# DRIVER_5V.net
KiCad netlist of a schematic drawn in EAGLE
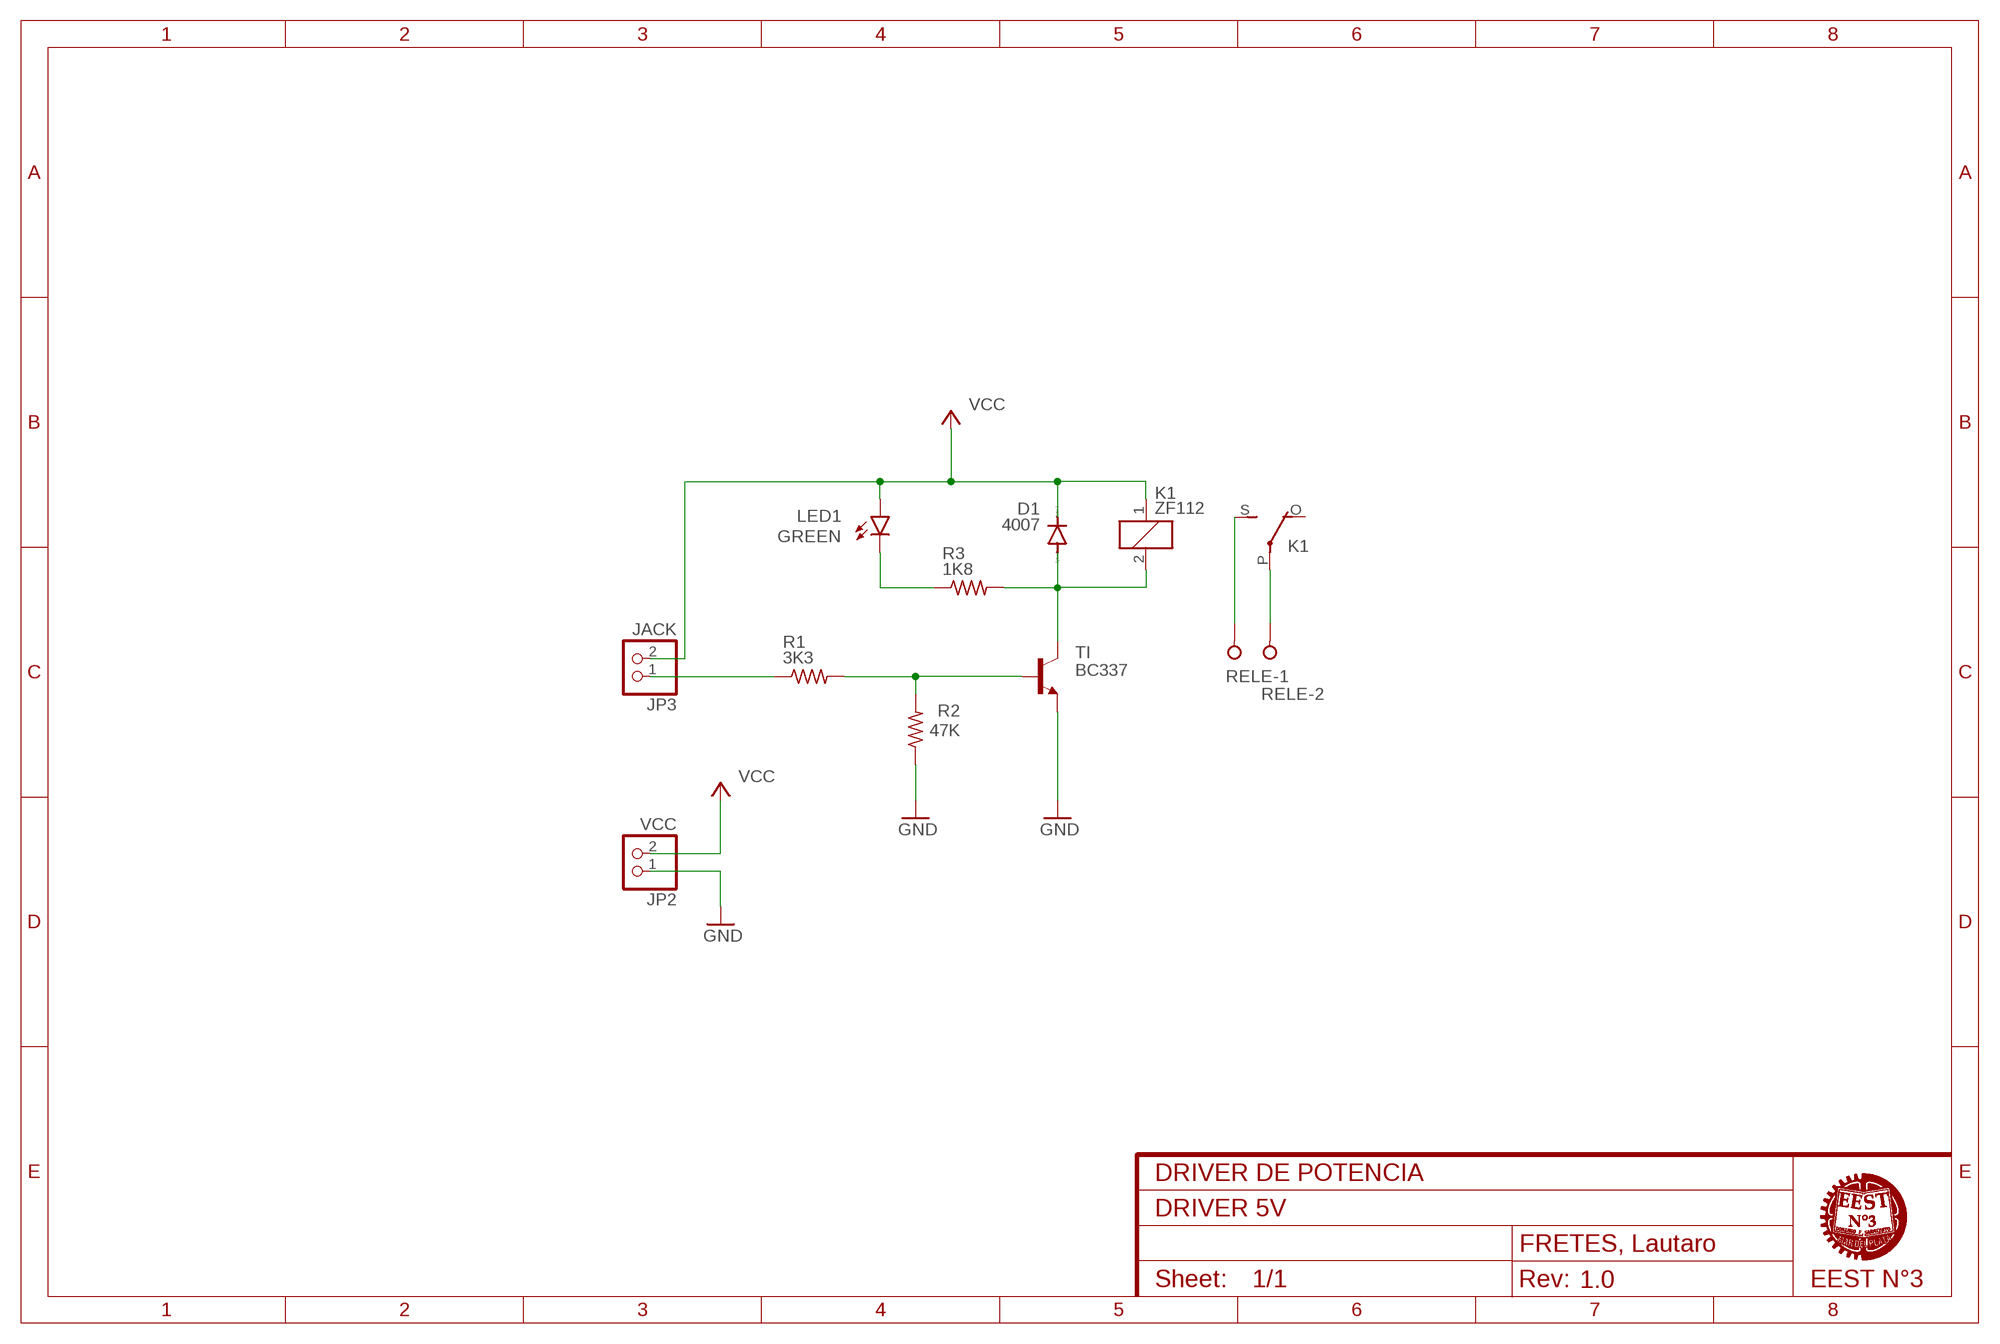
[diagram p0: schematic, sheet 1]

(export (version "E")
  (design (tool "Eeschema 10.0.6"))
  (components
    (comp (ref "D1")
      (value "4007")
      (footprint "eagle-import:DO35-10")
      (libsource (lib "eagle-import") (part "1N4148DO35-10"))
    )
    (comp (ref "JP2")
      (value "VCC")
      (footprint "eagle-import:1X02")
      (libsource (lib "eagle-import") (part "PINHD-1X2"))
    )
    (comp (ref "JP3")
      (value "JACK")
      (footprint "eagle-import:1X02")
      (libsource (lib "eagle-import") (part "PINHD-1X2"))
    )
    (comp (ref "K1")
      (value "ZF112")
      (footprint "eagle-import:ZF112")
      (libsource (lib "eagle-import") (part "ZF112"))
    )
    (comp (ref "LED1")
      (value "GREEN")
      (footprint "eagle-import:LED5MM")
      (libsource (lib "eagle-import") (part "LED5MM"))
    )
    (comp (ref "R1")
      (value "3K3")
      (footprint "eagle-import:0207_10")
      (libsource (lib "eagle-import") (part "R-US_0207/10"))
    )
    (comp (ref "R2")
      (value "47K")
      (footprint "eagle-import:0207_10")
      (libsource (lib "eagle-import") (part "R-US_0207/10"))
    )
    (comp (ref "R3")
      (value "1K8")
      (footprint "eagle-import:0207_10")
      (libsource (lib "eagle-import") (part "R-US_0207/10"))
    )
    (comp (ref "RELE")
      (value "W237-02P")
      (footprint "eagle-import:W237-132")
      (libsource (lib "eagle-import") (part "W237-02P"))
    )
    (comp (ref "TI")
      (value "BC337")
      (footprint "eagle-import:TO92-CBE")
      (libsource (lib "eagle-import") (part "-NPN-TO92-CBE2N4124"))
    )
    (comp (ref "U$1")
      (value "LOGO_EEST_N3")
      (footprint "eagle-import:LOGO_EEST_N3_250")
      (libsource (lib "eagle-import") (part "LOGO_EEST_N3"))
    )
  )
  (nets
    (net (code "1") (name "GND") (class "Default")
      (node (ref "JP2") (pin "1") (pinfunction "1_1") (pintype "passive"))
      (node (ref "R2") (pin "1") (pinfunction "1_1") (pintype "passive"))
      (node (ref "TI") (pin "E") (pinfunction "E_E") (pintype "passive"))
    )
    (net (code "2") (name "Net-(D1-PadA)") (class "Default")
      (node (ref "D1") (pin "A") (pinfunction "A_A") (pintype "passive"))
      (node (ref "K1") (pin "2") (pinfunction "2_2") (pintype "passive"))
      (node (ref "R3") (pin "2") (pinfunction "2_2") (pintype "passive"))
      (node (ref "TI") (pin "C") (pinfunction "C_C") (pintype "passive"))
    )
    (net (code "3") (name "Net-(JP3-Pad1)") (class "Default")
      (node (ref "JP3") (pin "1") (pinfunction "1_1") (pintype "passive"))
      (node (ref "R1") (pin "1") (pinfunction "1_1") (pintype "passive"))
    )
    (net (code "4") (name "Net-(LED1-C)") (class "Default")
      (node (ref "LED1") (pin "K") (pinfunction "C_K") (pintype "passive"))
      (node (ref "R3") (pin "1") (pinfunction "1_1") (pintype "passive"))
    )
    (net (code "5") (name "Net-(R1-Pad2)") (class "Default")
      (node (ref "R1") (pin "2") (pinfunction "2_2") (pintype "passive"))
      (node (ref "R2") (pin "2") (pinfunction "2_2") (pintype "passive"))
      (node (ref "TI") (pin "B") (pinfunction "B_B") (pintype "passive"))
    )
    (net (code "6") (name "Net-(RELEA-KL)") (class "Default")
      (node (ref "K1") (pin "S") (pinfunction "S_S") (pintype "passive"))
      (node (ref "RELE") (pin "1") (pinfunction "KL_1") (pintype "passive"))
    )
    (net (code "7") (name "Net-(RELEB-KL)") (class "Default")
      (node (ref "K1") (pin "P") (pinfunction "P_P") (pintype "passive"))
      (node (ref "RELE") (pin "2") (pinfunction "KL_2") (pintype "passive"))
    )
    (net (code "8") (name "VCC") (class "Default")
      (node (ref "D1") (pin "C") (pinfunction "C_C") (pintype "passive"))
      (node (ref "JP2") (pin "2") (pinfunction "2_2") (pintype "passive"))
      (node (ref "JP3") (pin "2") (pinfunction "2_2") (pintype "passive"))
      (node (ref "K1") (pin "1") (pinfunction "1_1") (pintype "passive"))
      (node (ref "LED1") (pin "A") (pinfunction "A_A") (pintype "passive"))
    )
    (net (code "9") (name "unconnected-(K1-PadO)") (class "Default")
      (node (ref "K1") (pin "O") (pinfunction "O_O") (pintype "passive"))
    )
  )
)
